# transceiver.net
KiCad netlist of a schematic drawn in Altium Designer
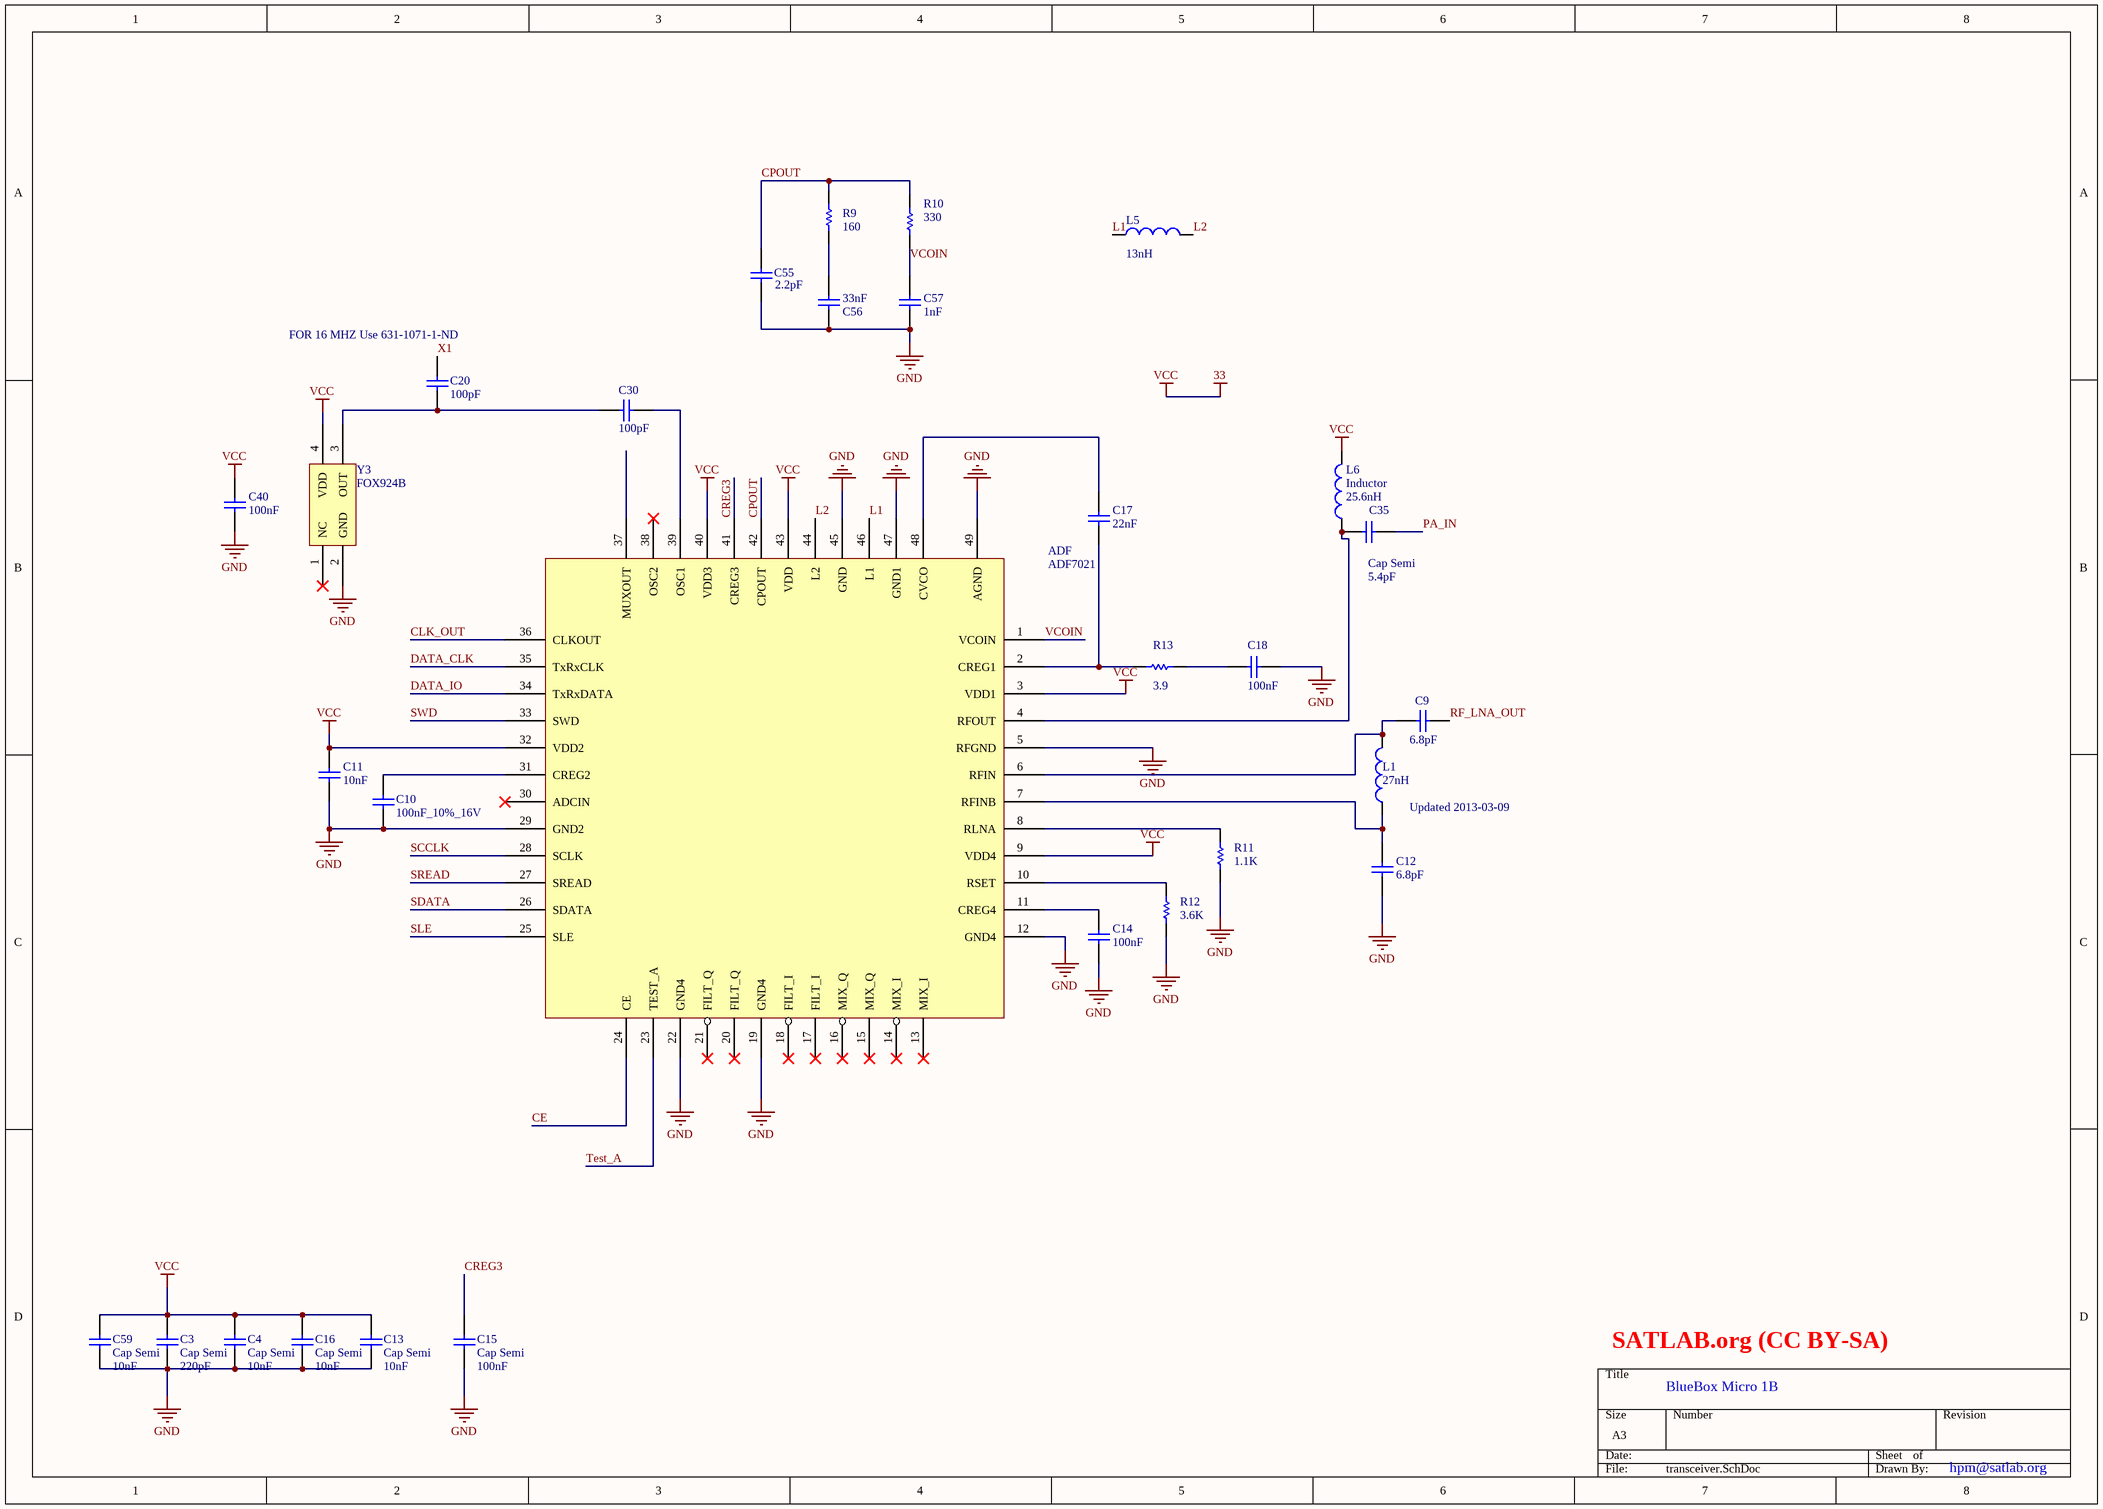
[diagram p0: transceiver.SchDoc]

(export (version "E")
  (design (tool "Eeschema 10.0.6"))
  (components
    (comp (ref "ADF")
      (value "ADF7021")
      (footprint "QFN50P700X700X100-48M")
      (description "ADF7021 transceiver")
      (fields (field (name "BY") "Nikolaj Bisgaard Pedersen"))
      (libsource (lib "common") (part "ADF7021"))
    )
    (comp (ref "C3")
      (value "Cap Semi")
      (footprint "C06")
      (description "Capacitor (Semiconductor SIM Model)")
      (fields (field (name "ALTIUM_VALUE") "220pF") (field (name "PUBLISHER") "Altium Limited"))
      (libsource (lib "common") (part "Capacitor"))
    )
    (comp (ref "C4")
      (value "Cap Semi")
      (footprint "C06")
      (description "Capacitor (Semiconductor SIM Model)")
      (fields (field (name "ALTIUM_VALUE") "10nF") (field (name "PUBLISHER") "Altium Limited"))
      (libsource (lib "common") (part "Capacitor"))
    )
    (comp (ref "C9")
      (value "6.8pF")
      (footprint "C06")
      (description "Capacitor (Semiconductor SIM Model)")
      (fields (field (name "Comment") "Cap Semi") (field (name "PUBLISHER") "Altium Limited"))
      (libsource (lib "common") (part "Capacitor"))
    )
    (comp (ref "C10")
      (value "100nF_10%_16V")
      (footprint "C04")
      (description "Capacitor, standard")
      (fields (field (name "Comment") "Capacitor"))
      (libsource (lib "misc-passive") (part "Capacitor"))
    )
    (comp (ref "C11")
      (value "10nF")
      (footprint "C06")
      (description "Capacitor (Semiconductor SIM Model)")
      (fields (field (name "Comment") "Cap Semi") (field (name "PUBLISHER") "Altium Limited"))
      (libsource (lib "common") (part "Capacitor"))
    )
    (comp (ref "C12")
      (value "6.8pF")
      (footprint "C06")
      (description "Capacitor (Semiconductor SIM Model)")
      (fields (field (name "Comment") "Cap Semi") (field (name "PUBLISHER") "Altium Limited"))
      (libsource (lib "common") (part "Capacitor"))
    )
    (comp (ref "C13")
      (value "Cap Semi")
      (footprint "C06")
      (description "Capacitor (Semiconductor SIM Model)")
      (fields (field (name "ALTIUM_VALUE") "10nF") (field (name "PUBLISHER") "Altium Limited"))
      (libsource (lib "common") (part "Capacitor"))
    )
    (comp (ref "C14")
      (value "100nF")
      (footprint "C06")
      (description "Capacitor (Semiconductor SIM Model)")
      (fields (field (name "Comment") "Cap Semi") (field (name "PUBLISHER") "Altium Limited"))
      (libsource (lib "common") (part "Capacitor"))
    )
    (comp (ref "C15")
      (value "Cap Semi")
      (footprint "C06")
      (description "Capacitor (Semiconductor SIM Model)")
      (fields (field (name "ALTIUM_VALUE") "100nF") (field (name "PUBLISHER") "Altium Limited"))
      (libsource (lib "common") (part "Capacitor"))
    )
    (comp (ref "C16")
      (value "Cap Semi")
      (footprint "C06")
      (description "Capacitor (Semiconductor SIM Model)")
      (fields (field (name "ALTIUM_VALUE") "10nF") (field (name "PUBLISHER") "Altium Limited"))
      (libsource (lib "common") (part "Capacitor"))
    )
    (comp (ref "C17")
      (value "22nF")
      (footprint "C06")
      (description "Capacitor (Semiconductor SIM Model)")
      (fields (field (name "Comment") "Cap Semi") (field (name "PUBLISHER") "Altium Limited"))
      (libsource (lib "common") (part "Capacitor"))
    )
    (comp (ref "C18")
      (value "100nF")
      (footprint "C06")
      (description "Capacitor (Semiconductor SIM Model)")
      (fields (field (name "Comment") "Cap Semi") (field (name "PUBLISHER") "Altium Limited"))
      (libsource (lib "common") (part "Capacitor"))
    )
    (comp (ref "C20")
      (value "100pF")
      (footprint "C04")
      (description "Capacitor, standard")
      (fields (field (name "Comment") "Capacitor"))
      (libsource (lib "misc-passive") (part "Capacitor"))
    )
    (comp (ref "C30")
      (value "100pF")
      (footprint "C04")
      (description "Capacitor, standard")
      (fields (field (name "Comment") "Capacitor"))
      (libsource (lib "misc-passive") (part "Capacitor"))
    )
    (comp (ref "C35")
      (value "Cap Semi")
      (footprint "C06")
      (description "Capacitor (Semiconductor SIM Model)")
      (fields (field (name "ALTIUM_VALUE") "5.4pF") (field (name "PUBLISHER") "Altium Limited"))
      (libsource (lib "common") (part "Capacitor"))
    )
    (comp (ref "C40")
      (value "100nF")
      (footprint "C06")
      (description "Capacitor (Semiconductor SIM Model)")
      (fields (field (name "Comment") "Cap Semi") (field (name "PUBLISHER") "Altium Limited"))
      (libsource (lib "common") (part "Capacitor"))
    )
    (comp (ref "C55")
      (value "2.2pF")
      (footprint "C06")
      (description "Capacitor (Semiconductor SIM Model)")
      (fields (field (name "Comment") "Cap Semi") (field (name "PUBLISHER") "Altium Limited"))
      (libsource (lib "common") (part "Capacitor"))
    )
    (comp (ref "C56")
      (value "33nF")
      (footprint "C06")
      (description "Capacitor (Semiconductor SIM Model)")
      (fields (field (name "Comment") "Cap Semi") (field (name "PUBLISHER") "Altium Limited"))
      (libsource (lib "common") (part "Capacitor"))
    )
    (comp (ref "C57")
      (value "1nF")
      (footprint "C06")
      (description "Capacitor (Semiconductor SIM Model)")
      (fields (field (name "Comment") "Cap Semi") (field (name "PUBLISHER") "Altium Limited"))
      (libsource (lib "common") (part "Capacitor"))
    )
    (comp (ref "C59")
      (value "Cap Semi")
      (footprint "C06")
      (description "Capacitor (Semiconductor SIM Model)")
      (fields (field (name "ALTIUM_VALUE") "10nF") (field (name "PUBLISHER") "Altium Limited"))
      (libsource (lib "common") (part "Capacitor"))
    )
    (comp (ref "L1")
      (value "27nH")
      (footprint "C06")
      (fields (field (name "Comment") "Inductor") (field (name "PUBLISHER") "<HP>"))
      (libsource (lib "common") (part "Inductor"))
    )
    (comp (ref "L5")
      (value "13nH")
      (footprint "L06")
      (description "Inductor")
      (fields (field (name "PUBLISHER") "Altium Limited"))
      (libsource (lib "Miscellaneous Devices") (part "Inductor"))
    )
    (comp (ref "L6")
      (value "Inductor")
      (footprint "C06")
      (fields (field (name "ALTIUM_VALUE") "25.6nH") (field (name "PUBLISHER") "<HP>"))
      (libsource (lib "common") (part "Inductor"))
    )
    (comp (ref "R9")
      (value "160")
      (footprint "R06")
      (description "Semiconductor Resistor")
      (fields (field (name "Comment") "Res Semi") (field (name "PUBLISHER") "Altium Limited"))
      (libsource (lib "common") (part "Resistor"))
    )
    (comp (ref "R10")
      (value "330")
      (footprint "R06")
      (description "Semiconductor Resistor")
      (fields (field (name "Comment") "Res Semi") (field (name "PUBLISHER") "Altium Limited"))
      (libsource (lib "common") (part "Resistor"))
    )
    (comp (ref "R11")
      (value "1.1K")
      (footprint "R06")
      (description "Semiconductor Resistor")
      (fields (field (name "Comment") "Res Semi") (field (name "PUBLISHER") "Altium Limited"))
      (libsource (lib "common") (part "Resistor"))
    )
    (comp (ref "R12")
      (value "3.6K")
      (footprint "R06")
      (description "Semiconductor Resistor")
      (fields (field (name "Comment") "Res Semi") (field (name "PUBLISHER") "Altium Limited"))
      (libsource (lib "common") (part "Resistor"))
    )
    (comp (ref "R13")
      (value "3.9")
      (footprint "R06")
      (description "Semiconductor Resistor")
      (fields (field (name "Comment") "Res Semi") (field (name "PUBLISHER") "Altium Limited"))
      (libsource (lib "common") (part "Resistor"))
    )
    (comp (ref "Y3")
      (value "FOX924B")
      (footprint "Fox924")
      (description "FOX924B TCXO 19.44 MHz")
      (fields (field (name "BY") "Nikolaj B. Pedersen") (field (name "USERNAME") "Markem"))
      (libsource (lib "common") (part "FOX924B"))
    )
  )
  (nets
    (net (code "1") (name "/CE") (class "Default")
      (node (ref "ADF") (pin "24") (pinfunction "CE_24") (pintype "passive"))
    )
    (net (code "2") (name "/CLK_OUT") (class "Default")
      (node (ref "ADF") (pin "36") (pinfunction "CLKOUT_36") (pintype "passive"))
    )
    (net (code "3") (name "/CPOUT") (class "Default")
      (node (ref "ADF") (pin "42") (pinfunction "CPOUT_42") (pintype "passive"))
      (node (ref "C55") (pin "2") (pinfunction "2_2") (pintype "passive"))
      (node (ref "R10") (pin "2") (pinfunction "2_2") (pintype "passive"))
      (node (ref "R9") (pin "2") (pinfunction "2_2") (pintype "passive"))
    )
    (net (code "4") (name "/CREG3") (class "Default")
      (node (ref "ADF") (pin "41") (pinfunction "CREG3_41") (pintype "passive"))
      (node (ref "C15") (pin "2") (pinfunction "2_2") (pintype "passive"))
    )
    (net (code "5") (name "/DATA_CLK") (class "Default")
      (node (ref "ADF") (pin "35") (pinfunction "TxRxCLK_35") (pintype "passive"))
    )
    (net (code "6") (name "/DATA_IO") (class "Default")
      (node (ref "ADF") (pin "34") (pinfunction "TxRxDATA_34") (pintype "passive"))
    )
    (net (code "7") (name "/L1") (class "Default")
      (node (ref "ADF") (pin "46") (pinfunction "L1_46") (pintype "passive"))
      (node (ref "L5") (pin "1") (pinfunction "1_1") (pintype "passive"))
    )
    (net (code "8") (name "/L2") (class "Default")
      (node (ref "ADF") (pin "44") (pinfunction "L2_44") (pintype "passive"))
      (node (ref "L5") (pin "2") (pinfunction "2_2") (pintype "passive"))
    )
    (net (code "9") (name "/PA_IN") (class "Default")
      (node (ref "C35") (pin "2") (pinfunction "2_2") (pintype "passive"))
    )
    (net (code "10") (name "/RF_LNA_OUT") (class "Default")
      (node (ref "C9") (pin "1") (pinfunction "1_1") (pintype "passive"))
    )
    (net (code "11") (name "/SCCLK") (class "Default")
      (node (ref "ADF") (pin "28") (pinfunction "SCLK_28") (pintype "passive"))
    )
    (net (code "12") (name "/SDATA") (class "Default")
      (node (ref "ADF") (pin "26") (pinfunction "SDATA_26") (pintype "passive"))
    )
    (net (code "13") (name "/SLE") (class "Default")
      (node (ref "ADF") (pin "25") (pinfunction "SLE_25") (pintype "passive"))
    )
    (net (code "14") (name "/SREAD") (class "Default")
      (node (ref "ADF") (pin "27") (pinfunction "SREAD_27") (pintype "passive"))
    )
    (net (code "15") (name "/SWD") (class "Default")
      (node (ref "ADF") (pin "33") (pinfunction "SWD_33") (pintype "passive"))
    )
    (net (code "16") (name "/Test_A") (class "Default")
      (node (ref "ADF") (pin "23") (pinfunction "TEST_A_23") (pintype "passive"))
    )
    (net (code "17") (name "/VCOIN") (class "Default")
      (node (ref "ADF") (pin "1") (pinfunction "VCOIN_1") (pintype "passive"))
      (node (ref "C57") (pin "2") (pinfunction "2_2") (pintype "passive"))
      (node (ref "R10") (pin "1") (pinfunction "1_1") (pintype "passive"))
    )
    (net (code "18") (name "/X1") (class "Default")
      (node (ref "C20") (pin "1") (pinfunction "1_1") (pintype "passive"))
    )
    (net (code "19") (name "33") (class "Default")
      (node (ref "ADF") (pin "3") (pinfunction "VDD1_3") (pintype "passive"))
      (node (ref "ADF") (pin "32") (pinfunction "VDD2_32") (pintype "passive"))
      (node (ref "ADF") (pin "40") (pinfunction "VDD3_40") (pintype "passive"))
      (node (ref "ADF") (pin "43") (pinfunction "VDD_43") (pintype "passive"))
      (node (ref "ADF") (pin "9") (pinfunction "VDD4_9") (pintype "passive"))
      (node (ref "C11") (pin "2") (pinfunction "2_2") (pintype "passive"))
      (node (ref "C13") (pin "2") (pinfunction "2_2") (pintype "passive"))
      (node (ref "C16") (pin "2") (pinfunction "2_2") (pintype "passive"))
      (node (ref "C3") (pin "2") (pinfunction "2_2") (pintype "passive"))
      (node (ref "C4") (pin "2") (pinfunction "2_2") (pintype "passive"))
      (node (ref "C40") (pin "2") (pinfunction "2_2") (pintype "passive"))
      (node (ref "C59") (pin "2") (pinfunction "2_2") (pintype "passive"))
      (node (ref "L6") (pin "2") (pinfunction "2_2") (pintype "passive"))
      (node (ref "Y3") (pin "4") (pinfunction "VDD_4") (pintype "passive"))
    )
    (net (code "20") (name "GND") (class "Default")
      (node (ref "ADF") (pin "12") (pinfunction "GND4_12") (pintype "passive"))
      (node (ref "ADF") (pin "19") (pinfunction "GND4_19") (pintype "passive"))
      (node (ref "ADF") (pin "22") (pinfunction "GND4_22") (pintype "passive"))
      (node (ref "ADF") (pin "29") (pinfunction "GND2_29") (pintype "passive"))
      (node (ref "ADF") (pin "45") (pinfunction "GND_45") (pintype "passive"))
      (node (ref "ADF") (pin "47") (pinfunction "GND1_47") (pintype "passive"))
      (node (ref "ADF") (pin "49") (pinfunction "AGND_49") (pintype "passive"))
      (node (ref "ADF") (pin "5") (pinfunction "RFGND_5") (pintype "passive"))
      (node (ref "C10") (pin "1") (pinfunction "1_1") (pintype "passive"))
      (node (ref "C11") (pin "1") (pinfunction "1_1") (pintype "passive"))
      (node (ref "C12") (pin "1") (pinfunction "1_1") (pintype "passive"))
      (node (ref "C13") (pin "1") (pinfunction "1_1") (pintype "passive"))
      (node (ref "C14") (pin "1") (pinfunction "1_1") (pintype "passive"))
      (node (ref "C15") (pin "1") (pinfunction "1_1") (pintype "passive"))
      (node (ref "C16") (pin "1") (pinfunction "1_1") (pintype "passive"))
      (node (ref "C18") (pin "2") (pinfunction "2_2") (pintype "passive"))
      (node (ref "C3") (pin "1") (pinfunction "1_1") (pintype "passive"))
      (node (ref "C4") (pin "1") (pinfunction "1_1") (pintype "passive"))
      (node (ref "C40") (pin "1") (pinfunction "1_1") (pintype "passive"))
      (node (ref "C55") (pin "1") (pinfunction "1_1") (pintype "passive"))
      (node (ref "C56") (pin "1") (pinfunction "1_1") (pintype "passive"))
      (node (ref "C57") (pin "1") (pinfunction "1_1") (pintype "passive"))
      (node (ref "C59") (pin "1") (pinfunction "1_1") (pintype "passive"))
      (node (ref "R11") (pin "2") (pinfunction "2_2") (pintype "passive"))
      (node (ref "R12") (pin "1") (pinfunction "1_1") (pintype "passive"))
      (node (ref "Y3") (pin "2") (pinfunction "GND_2") (pintype "passive"))
    )
    (net (code "21") (name "Net-(ADF-CREG1)") (class "Default")
      (node (ref "ADF") (pin "2") (pinfunction "CREG1_2") (pintype "passive"))
      (node (ref "C17") (pin "1") (pinfunction "1_1") (pintype "passive"))
      (node (ref "R13") (pin "1") (pinfunction "1_1") (pintype "passive"))
    )
    (net (code "22") (name "Net-(ADF-CREG2)") (class "Default")
      (node (ref "ADF") (pin "31") (pinfunction "CREG2_31") (pintype "passive"))
      (node (ref "C10") (pin "2") (pinfunction "2_2") (pintype "passive"))
    )
    (net (code "23") (name "Net-(ADF-CREG4)") (class "Default")
      (node (ref "ADF") (pin "11") (pinfunction "CREG4_11") (pintype "passive"))
      (node (ref "C14") (pin "2") (pinfunction "2_2") (pintype "passive"))
    )
    (net (code "24") (name "Net-(ADF-CVCO)") (class "Default")
      (node (ref "ADF") (pin "48") (pinfunction "CVCO_48") (pintype "passive"))
      (node (ref "C17") (pin "2") (pinfunction "2_2") (pintype "passive"))
    )
    (net (code "25") (name "Net-(ADF-OSC1)") (class "Default")
      (node (ref "ADF") (pin "39") (pinfunction "OSC1_39") (pintype "passive"))
      (node (ref "C30") (pin "1") (pinfunction "1_1") (pintype "passive"))
    )
    (net (code "26") (name "Net-(ADF-RFIN)") (class "Default")
      (node (ref "ADF") (pin "6") (pinfunction "RFIN_6") (pintype "passive"))
      (node (ref "C9") (pin "2") (pinfunction "2_2") (pintype "passive"))
      (node (ref "L1") (pin "2") (pinfunction "2_2") (pintype "passive"))
    )
    (net (code "27") (name "Net-(ADF-RFINB)") (class "Default")
      (node (ref "ADF") (pin "7") (pinfunction "RFINB_7") (pintype "passive"))
      (node (ref "C12") (pin "2") (pinfunction "2_2") (pintype "passive"))
      (node (ref "L1") (pin "1") (pinfunction "1_1") (pintype "passive"))
    )
    (net (code "28") (name "Net-(ADF-RFOUT)") (class "Default")
      (node (ref "ADF") (pin "4") (pinfunction "RFOUT_4") (pintype "passive"))
      (node (ref "C35") (pin "1") (pinfunction "1_1") (pintype "passive"))
      (node (ref "L6") (pin "1") (pinfunction "1_1") (pintype "passive"))
    )
    (net (code "29") (name "Net-(ADF-RLNA)") (class "Default")
      (node (ref "ADF") (pin "8") (pinfunction "RLNA_8") (pintype "passive"))
      (node (ref "R11") (pin "1") (pinfunction "1_1") (pintype "passive"))
    )
    (net (code "30") (name "Net-(ADF-RSET)") (class "Default")
      (node (ref "ADF") (pin "10") (pinfunction "RSET_10") (pintype "passive"))
      (node (ref "R12") (pin "2") (pinfunction "2_2") (pintype "passive"))
    )
    (net (code "31") (name "Net-(C18-Pad1)") (class "Default")
      (node (ref "C18") (pin "1") (pinfunction "1_1") (pintype "passive"))
      (node (ref "R13") (pin "2") (pinfunction "2_2") (pintype "passive"))
    )
    (net (code "32") (name "Net-(C56-Pad2)") (class "Default")
      (node (ref "C56") (pin "2") (pinfunction "2_2") (pintype "passive"))
      (node (ref "R9") (pin "1") (pinfunction "1_1") (pintype "passive"))
    )
    (net (code "33") (name "Net-(Y3-OUT)") (class "Default")
      (node (ref "C20") (pin "2") (pinfunction "2_2") (pintype "passive"))
      (node (ref "C30") (pin "2") (pinfunction "2_2") (pintype "passive"))
      (node (ref "Y3") (pin "3") (pinfunction "OUT_3") (pintype "passive"))
    )
    (net (code "34") (name "unconnected-(ADF-ADCIN-Pad30)") (class "Default")
      (node (ref "ADF") (pin "30") (pinfunction "ADCIN_30") (pintype "passive+no_connect"))
    )
    (net (code "35") (name "unconnected-(ADF-FILT_I-Pad17)") (class "Default")
      (node (ref "ADF") (pin "17") (pinfunction "FILT_I_17") (pintype "passive+no_connect"))
    )
    (net (code "36") (name "unconnected-(ADF-FILT_I-Pad18)") (class "Default")
      (node (ref "ADF") (pin "18") (pinfunction "FILT_I_18") (pintype "passive+no_connect"))
    )
    (net (code "37") (name "unconnected-(ADF-FILT_Q-Pad20)") (class "Default")
      (node (ref "ADF") (pin "20") (pinfunction "FILT_Q_20") (pintype "passive+no_connect"))
    )
    (net (code "38") (name "unconnected-(ADF-FILT_Q-Pad21)") (class "Default")
      (node (ref "ADF") (pin "21") (pinfunction "FILT_Q_21") (pintype "passive+no_connect"))
    )
    (net (code "39") (name "unconnected-(ADF-MIX_I-Pad13)") (class "Default")
      (node (ref "ADF") (pin "13") (pinfunction "MIX_I_13") (pintype "passive+no_connect"))
    )
    (net (code "40") (name "unconnected-(ADF-MIX_I-Pad14)") (class "Default")
      (node (ref "ADF") (pin "14") (pinfunction "MIX_I_14") (pintype "passive+no_connect"))
    )
    (net (code "41") (name "unconnected-(ADF-MIX_Q-Pad15)") (class "Default")
      (node (ref "ADF") (pin "15") (pinfunction "MIX_Q_15") (pintype "passive+no_connect"))
    )
    (net (code "42") (name "unconnected-(ADF-MIX_Q-Pad16)") (class "Default")
      (node (ref "ADF") (pin "16") (pinfunction "MIX_Q_16") (pintype "passive+no_connect"))
    )
    (net (code "43") (name "unconnected-(ADF-MUXOUT-Pad37)") (class "Default")
      (node (ref "ADF") (pin "37") (pinfunction "MUXOUT_37") (pintype "passive"))
    )
    (net (code "44") (name "unconnected-(ADF-OSC2-Pad38)") (class "Default")
      (node (ref "ADF") (pin "38") (pinfunction "OSC2_38") (pintype "passive+no_connect"))
    )
    (net (code "45") (name "unconnected-(Y3-NC-Pad1)") (class "Default")
      (node (ref "Y3") (pin "1") (pinfunction "NC_1") (pintype "passive+no_connect"))
    )
  )
)
